# Power_Relay.net
KiCad netlist of a schematic drawn in Altium Designer
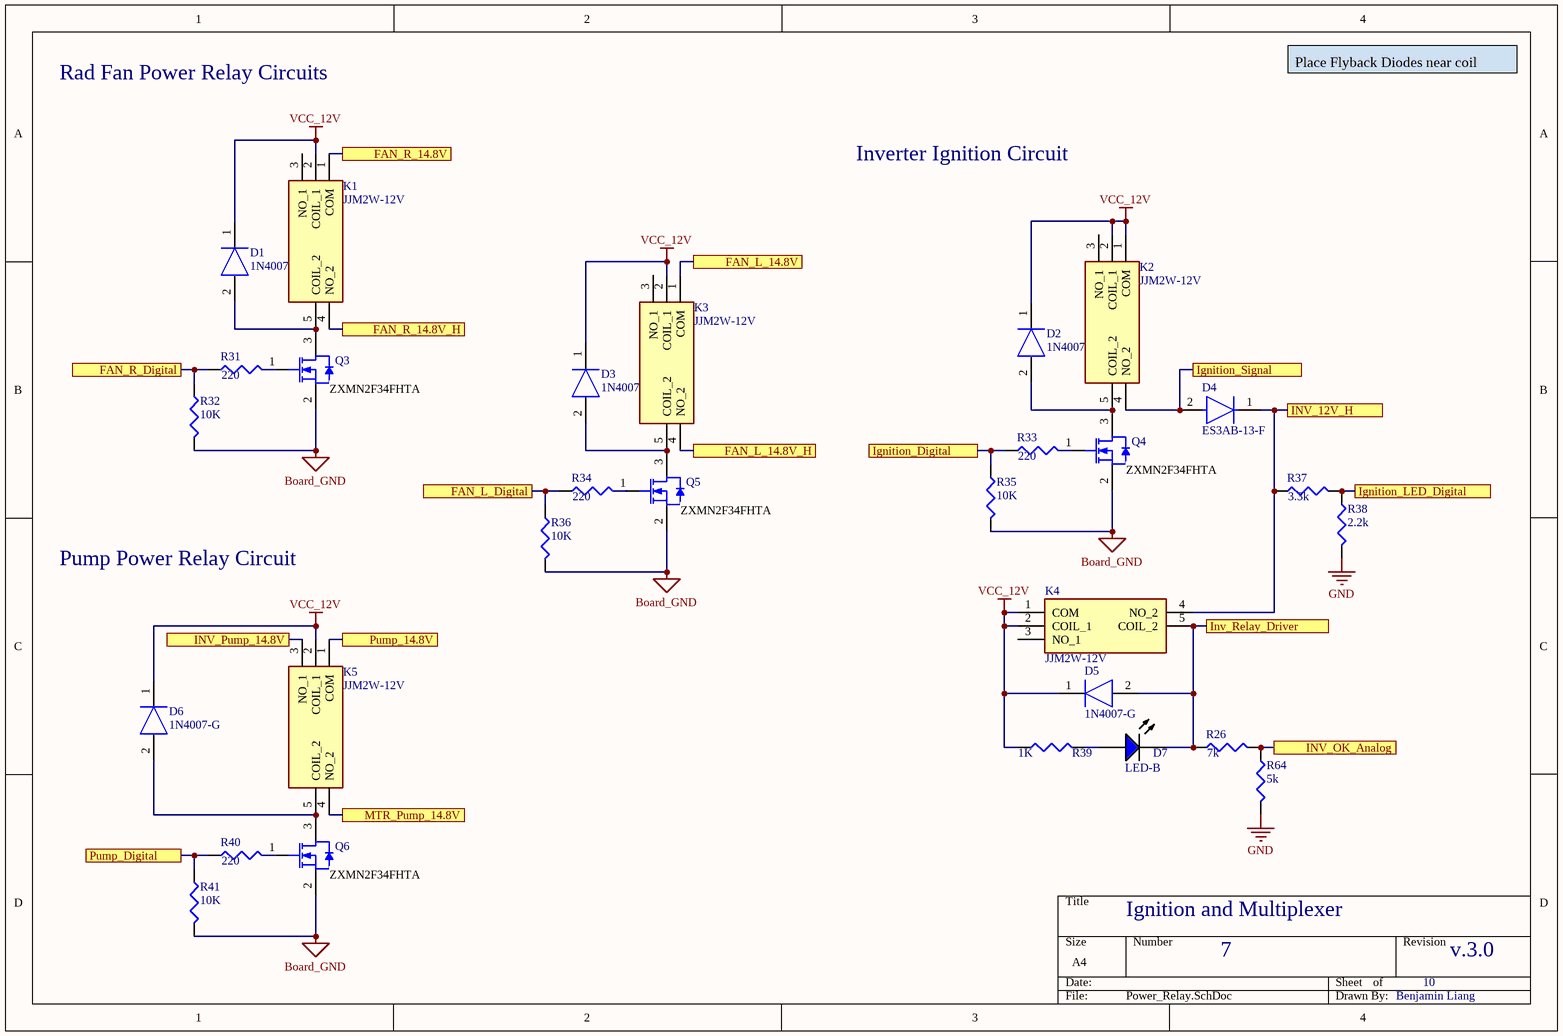
[diagram p0: Power_Relay.SchDoc]

(export (version "E")
  (design (tool "Eeschema 10.0.6"))
  (components
    (comp (ref "D1")
      (value "1N4007-G")
      (footprint "SamacSys:DIOAD1410W90L470D235")
      (description "Diode")
      (fields (field (name "MOUSER PART NUMBER") "750-1N4007-G"))
      (libsource (lib "*") (part "1N4007-G"))
    )
    (comp (ref "D2")
      (value "1N4007-G")
      (footprint "SamacSys:DIOAD1410W90L470D235")
      (description "Diode")
      (fields (field (name "MOUSER PART NUMBER") "750-1N4007-G"))
      (libsource (lib "*") (part "1N4007-G"))
    )
    (comp (ref "D3")
      (value "1N4007-G")
      (footprint "SamacSys:DIOAD1410W90L470D235")
      (description "Diode")
      (fields (field (name "MOUSER PART NUMBER") "750-1N4007-G"))
      (libsource (lib "*") (part "1N4007-G"))
    )
    (comp (ref "D4")
      (value "ES3AB-13-F")
      (footprint "FP-SMB-MFG")
      (description "DIODE GEN PURP 50V 3A SMB")
      (fields
        (field (name "OCTOPART") "https://octopart.com/es3ab-13-f-diodes+inc.-328916")
        (field (name "MANUFACTURER") "Diodes")
      )
      (libsource (lib "Altium Content Vault") (part "d7152d700b627762746794eb795d46e"))
    )
    (comp (ref "D5")
      (value "1N4007-G")
      (footprint "SamacSys:DIOAD1410W90L470D235")
      (description "Diode")
      (fields (field (name "MOUSER PART NUMBER") "750-1N4007-G"))
      (libsource (lib "*") (part "1N4007-G"))
    )
    (comp (ref "D6")
      (value "1N4007-G")
      (footprint "SamacSys:DIOAD1410W90L470D235")
      (description "Diode")
      (fields (field (name "MOUSER PART NUMBER") "750-1N4007-G"))
      (libsource (lib "*") (part "1N4007-G"))
    )
    (comp (ref "D7")
      (value "LED-B")
      (footprint "LTST-C193TBKT_V")
      (fields (field (name "MANUFACTURER") "Lite-On"))
      (libsource (lib "Altium Content Vault") (part "LED-BLUE-AK-2"))
    )
    (comp (ref "K1")
      (value "JJM2W-12V")
      (footprint "SamacSys:JJM2W12V")
      (description "Relay or Contactor")
      (fields (field (name "MOUSER PART NUMBER") "769-JJM2W-12V"))
      (libsource (lib "*") (part "JJM2W-12V"))
    )
    (comp (ref "K2")
      (value "JJM2W-12V")
      (footprint "SamacSys:JJM2W12V")
      (description "Relay or Contactor")
      (fields (field (name "MOUSER PART NUMBER") "769-JJM2W-12V"))
      (libsource (lib "*") (part "JJM2W-12V"))
    )
    (comp (ref "K3")
      (value "JJM2W-12V")
      (footprint "SamacSys:JJM2W12V")
      (description "Relay or Contactor")
      (fields (field (name "MOUSER PART NUMBER") "769-JJM2W-12V"))
      (libsource (lib "*") (part "JJM2W-12V"))
    )
    (comp (ref "K4")
      (value "JJM2W-12V")
      (footprint "SamacSys:JJM2W12V")
      (description "Relay or Contactor")
      (fields (field (name "MOUSER PART NUMBER") "769-JJM2W-12V"))
      (libsource (lib "") (part "JJM2W-12V_1"))
    )
    (comp (ref "K5")
      (value "JJM2W-12V")
      (footprint "SamacSys:JJM2W12V")
      (description "Relay or Contactor")
      (fields (field (name "MOUSER PART NUMBER") "769-JJM2W-12V"))
      (libsource (lib "*") (part "JJM2W-12V"))
    )
    (comp (ref "Q3")
      (value "ZXMN2F34FHTA")
      (footprint "FAIR-SSOT3L-3_V")
      (fields (field (name "MANUFACTURER") "FairchildSemiconductor"))
      (libsource (lib "Altium Content Vault") (part "NEMOS-GSD-3"))
    )
    (comp (ref "Q4")
      (value "ZXMN2F34FHTA")
      (footprint "FAIR-SSOT3L-3_V")
      (fields (field (name "MANUFACTURER") "FairchildSemiconductor"))
      (libsource (lib "Altium Content Vault") (part "NEMOS-GSD-3"))
    )
    (comp (ref "Q5")
      (value "ZXMN2F34FHTA")
      (footprint "FAIR-SSOT3L-3_V")
      (fields (field (name "MANUFACTURER") "FairchildSemiconductor"))
      (libsource (lib "Altium Content Vault") (part "NEMOS-GSD-3"))
    )
    (comp (ref "Q6")
      (value "ZXMN2F34FHTA")
      (footprint "FAIR-SSOT3L-3_V")
      (fields (field (name "MANUFACTURER") "FairchildSemiconductor"))
      (libsource (lib "Altium Content Vault") (part "NEMOS-GSD-3"))
    )
    (comp (ref "R26")
      (value "7k")
      (footprint "J1-0603")
      (description "Resistor")
      (fields (field (name "PUBLISHER") "Altium Limited"))
      (libsource (lib "Miscellaneous Devices") (part "Res3"))
    )
    (comp (ref "R31")
      (value "220")
      (footprint "J1-0603")
      (description "Resistor")
      (fields (field (name "PUBLISHER") "Altium Limited"))
      (libsource (lib "Miscellaneous Devices") (part "Res3"))
    )
    (comp (ref "R32")
      (value "10K")
      (footprint "J1-0603")
      (description "Resistor")
      (fields (field (name "PUBLISHER") "Altium Limited"))
      (libsource (lib "Miscellaneous Devices") (part "Res3"))
    )
    (comp (ref "R33")
      (value "220")
      (footprint "J1-0603")
      (description "Resistor")
      (fields (field (name "PUBLISHER") "Altium Limited"))
      (libsource (lib "Miscellaneous Devices") (part "Res3"))
    )
    (comp (ref "R34")
      (value "220")
      (footprint "J1-0603")
      (description "Resistor")
      (fields (field (name "PUBLISHER") "Altium Limited"))
      (libsource (lib "Miscellaneous Devices") (part "Res3"))
    )
    (comp (ref "R35")
      (value "10K")
      (footprint "J1-0603")
      (description "Resistor")
      (fields (field (name "PUBLISHER") "Altium Limited"))
      (libsource (lib "Miscellaneous Devices") (part "Res3"))
    )
    (comp (ref "R36")
      (value "10K")
      (footprint "J1-0603")
      (description "Resistor")
      (fields (field (name "PUBLISHER") "Altium Limited"))
      (libsource (lib "Miscellaneous Devices") (part "Res3"))
    )
    (comp (ref "R37")
      (value "3.3k")
      (footprint "J1-0603")
      (description "Resistor")
      (fields (field (name "PUBLISHER") "Altium Limited"))
      (libsource (lib "Miscellaneous Devices") (part "Res3"))
    )
    (comp (ref "R38")
      (value "2.2k")
      (footprint "J1-0603")
      (description "Resistor")
      (fields (field (name "PUBLISHER") "Altium Limited"))
      (libsource (lib "Miscellaneous Devices") (part "Res3"))
    )
    (comp (ref "R39")
      (value "1K")
      (footprint "J1-0603")
      (description "Resistor")
      (fields (field (name "PUBLISHER") "Altium Limited"))
      (libsource (lib "Miscellaneous Devices") (part "Res3"))
    )
    (comp (ref "R40")
      (value "220")
      (footprint "J1-0603")
      (description "Resistor")
      (fields (field (name "PUBLISHER") "Altium Limited"))
      (libsource (lib "Miscellaneous Devices") (part "Res3"))
    )
    (comp (ref "R41")
      (value "10K")
      (footprint "J1-0603")
      (description "Resistor")
      (fields (field (name "PUBLISHER") "Altium Limited"))
      (libsource (lib "Miscellaneous Devices") (part "Res3"))
    )
    (comp (ref "R64")
      (value "5k")
      (footprint "J1-0603")
      (description "Resistor")
      (fields (field (name "PUBLISHER") "Altium Limited"))
      (libsource (lib "Miscellaneous Devices") (part "Res3"))
    )
  )
  (nets
    (net (code "1") (name "/FAN_L_14.8V") (class "Default")
      (node (ref "K3") (pin "1") (pinfunction "COM_1") (pintype "passive"))
    )
    (net (code "2") (name "/FAN_L_14.8V_H") (class "Default")
      (node (ref "K3") (pin "4") (pinfunction "NO_2_4") (pintype "passive"))
    )
    (net (code "3") (name "/FAN_L_Digital") (class "Default")
      (node (ref "R34") (pin "1") (pinfunction "1_1") (pintype "passive"))
      (node (ref "R36") (pin "1") (pinfunction "1_1") (pintype "passive"))
    )
    (net (code "4") (name "/FAN_R_14.8V") (class "Default")
      (node (ref "K1") (pin "1") (pinfunction "COM_1") (pintype "passive"))
    )
    (net (code "5") (name "/FAN_R_14.8V_H") (class "Default")
      (node (ref "K1") (pin "4") (pinfunction "NO_2_4") (pintype "passive"))
    )
    (net (code "6") (name "/FAN_R_Digital") (class "Default")
      (node (ref "R31") (pin "1") (pinfunction "1_1") (pintype "passive"))
      (node (ref "R32") (pin "1") (pinfunction "1_1") (pintype "passive"))
    )
    (net (code "7") (name "/INV_12V_H") (class "Default")
      (node (ref "D4") (pin "1") (pinfunction "C_1") (pintype "passive"))
      (node (ref "K4") (pin "4") (pinfunction "NO_2_4") (pintype "passive"))
      (node (ref "R37") (pin "1") (pinfunction "1_1") (pintype "passive"))
    )
    (net (code "8") (name "/INV_OK_Analog") (class "Default")
      (node (ref "R26") (pin "2") (pinfunction "2_2") (pintype "passive"))
      (node (ref "R64") (pin "1") (pinfunction "1_1") (pintype "passive"))
    )
    (net (code "9") (name "/INV_Pump_14.8V") (class "Default")
      (node (ref "K5") (pin "3") (pinfunction "NO_1_3") (pintype "passive"))
    )
    (net (code "10") (name "/Ignition_Digital") (class "Default")
      (node (ref "R33") (pin "1") (pinfunction "1_1") (pintype "passive"))
      (node (ref "R35") (pin "1") (pinfunction "1_1") (pintype "passive"))
    )
    (net (code "11") (name "/Ignition_LED_Digital") (class "Default")
      (node (ref "R37") (pin "2") (pinfunction "2_2") (pintype "passive"))
      (node (ref "R38") (pin "1") (pinfunction "1_1") (pintype "passive"))
    )
    (net (code "12") (name "/Ignition_Signal") (class "Default")
      (node (ref "D4") (pin "2") (pinfunction "A_2") (pintype "passive"))
      (node (ref "K2") (pin "4") (pinfunction "NO_2_4") (pintype "passive"))
    )
    (net (code "13") (name "/Inv_Relay_Driver") (class "Default")
      (node (ref "D5") (pin "2") (pinfunction "A_2") (pintype "passive"))
      (node (ref "D7") (pin "2") (pinfunction "K_2") (pintype "passive"))
      (node (ref "K4") (pin "5") (pinfunction "COIL_2_5") (pintype "passive"))
      (node (ref "R26") (pin "1") (pinfunction "1_1") (pintype "passive"))
    )
    (net (code "14") (name "/MTR_Pump_14.8V") (class "Default")
      (node (ref "K5") (pin "4") (pinfunction "NO_2_4") (pintype "passive"))
    )
    (net (code "15") (name "/Pump_14.8V") (class "Default")
      (node (ref "K5") (pin "1") (pinfunction "COM_1") (pintype "passive"))
    )
    (net (code "16") (name "/Pump_Digital") (class "Default")
      (node (ref "R40") (pin "1") (pinfunction "1_1") (pintype "passive"))
      (node (ref "R41") (pin "1") (pinfunction "1_1") (pintype "passive"))
    )
    (net (code "17") (name "Board_GND") (class "Default")
      (node (ref "Q3") (pin "2") (pinfunction "S_2") (pintype "passive"))
      (node (ref "Q4") (pin "2") (pinfunction "S_2") (pintype "passive"))
      (node (ref "Q5") (pin "2") (pinfunction "S_2") (pintype "passive"))
      (node (ref "Q6") (pin "2") (pinfunction "S_2") (pintype "passive"))
      (node (ref "R32") (pin "2") (pinfunction "2_2") (pintype "passive"))
      (node (ref "R35") (pin "2") (pinfunction "2_2") (pintype "passive"))
      (node (ref "R36") (pin "2") (pinfunction "2_2") (pintype "passive"))
      (node (ref "R41") (pin "2") (pinfunction "2_2") (pintype "passive"))
    )
    (net (code "18") (name "GND") (class "Default")
      (node (ref "R38") (pin "2") (pinfunction "2_2") (pintype "passive"))
      (node (ref "R64") (pin "2") (pinfunction "2_2") (pintype "passive"))
    )
    (net (code "19") (name "Net-(D1-A)") (class "Default")
      (node (ref "D1") (pin "2") (pinfunction "A_2") (pintype "passive"))
      (node (ref "K1") (pin "5") (pinfunction "COIL_2_5") (pintype "passive"))
      (node (ref "Q3") (pin "3") (pinfunction "D_3") (pintype "passive"))
    )
    (net (code "20") (name "Net-(D2-A)") (class "Default")
      (node (ref "D2") (pin "2") (pinfunction "A_2") (pintype "passive"))
      (node (ref "K2") (pin "5") (pinfunction "COIL_2_5") (pintype "passive"))
      (node (ref "Q4") (pin "3") (pinfunction "D_3") (pintype "passive"))
    )
    (net (code "21") (name "Net-(D3-A)") (class "Default")
      (node (ref "D3") (pin "2") (pinfunction "A_2") (pintype "passive"))
      (node (ref "K3") (pin "5") (pinfunction "COIL_2_5") (pintype "passive"))
      (node (ref "Q5") (pin "3") (pinfunction "D_3") (pintype "passive"))
    )
    (net (code "22") (name "Net-(D6-A)") (class "Default")
      (node (ref "D6") (pin "2") (pinfunction "A_2") (pintype "passive"))
      (node (ref "K5") (pin "5") (pinfunction "COIL_2_5") (pintype "passive"))
      (node (ref "Q6") (pin "3") (pinfunction "D_3") (pintype "passive"))
    )
    (net (code "23") (name "Net-(D7-A)") (class "Default")
      (node (ref "D7") (pin "1") (pinfunction "A_1") (pintype "passive"))
      (node (ref "R39") (pin "2") (pinfunction "2_2") (pintype "passive"))
    )
    (net (code "24") (name "Net-(Q3-G)") (class "Default")
      (node (ref "Q3") (pin "1") (pinfunction "G_1") (pintype "passive"))
      (node (ref "R31") (pin "2") (pinfunction "2_2") (pintype "passive"))
    )
    (net (code "25") (name "Net-(Q4-G)") (class "Default")
      (node (ref "Q4") (pin "1") (pinfunction "G_1") (pintype "passive"))
      (node (ref "R33") (pin "2") (pinfunction "2_2") (pintype "passive"))
    )
    (net (code "26") (name "Net-(Q5-G)") (class "Default")
      (node (ref "Q5") (pin "1") (pinfunction "G_1") (pintype "passive"))
      (node (ref "R34") (pin "2") (pinfunction "2_2") (pintype "passive"))
    )
    (net (code "27") (name "Net-(Q6-G)") (class "Default")
      (node (ref "Q6") (pin "1") (pinfunction "G_1") (pintype "passive"))
      (node (ref "R40") (pin "2") (pinfunction "2_2") (pintype "passive"))
    )
    (net (code "28") (name "VCC_12V") (class "Default")
      (node (ref "D1") (pin "1") (pinfunction "K_1") (pintype "passive"))
      (node (ref "D2") (pin "1") (pinfunction "K_1") (pintype "passive"))
      (node (ref "D3") (pin "1") (pinfunction "K_1") (pintype "passive"))
      (node (ref "D5") (pin "1") (pinfunction "K_1") (pintype "passive"))
      (node (ref "D6") (pin "1") (pinfunction "K_1") (pintype "passive"))
      (node (ref "K1") (pin "2") (pinfunction "COIL_1_2") (pintype "passive"))
      (node (ref "K2") (pin "1") (pinfunction "COM_1") (pintype "passive"))
      (node (ref "K2") (pin "2") (pinfunction "COIL_1_2") (pintype "passive"))
      (node (ref "K3") (pin "2") (pinfunction "COIL_1_2") (pintype "passive"))
      (node (ref "K4") (pin "1") (pinfunction "COM_1") (pintype "passive"))
      (node (ref "K4") (pin "2") (pinfunction "COIL_1_2") (pintype "passive"))
      (node (ref "K5") (pin "2") (pinfunction "COIL_1_2") (pintype "passive"))
      (node (ref "R39") (pin "1") (pinfunction "1_1") (pintype "passive"))
    )
    (net (code "29") (name "unconnected-(K1-NO_1-Pad3)") (class "Default")
      (node (ref "K1") (pin "3") (pinfunction "NO_1_3") (pintype "passive"))
    )
    (net (code "30") (name "unconnected-(K2-NO_1-Pad3)") (class "Default")
      (node (ref "K2") (pin "3") (pinfunction "NO_1_3") (pintype "passive"))
    )
    (net (code "31") (name "unconnected-(K3-NO_1-Pad3)") (class "Default")
      (node (ref "K3") (pin "3") (pinfunction "NO_1_3") (pintype "passive"))
    )
    (net (code "32") (name "unconnected-(K4-NO_1-Pad3)") (class "Default")
      (node (ref "K4") (pin "3") (pinfunction "NO_1_3") (pintype "passive"))
    )
  )
)
